# Esquematico.net
KiCad netlist of a schematic drawn in Altium Designer
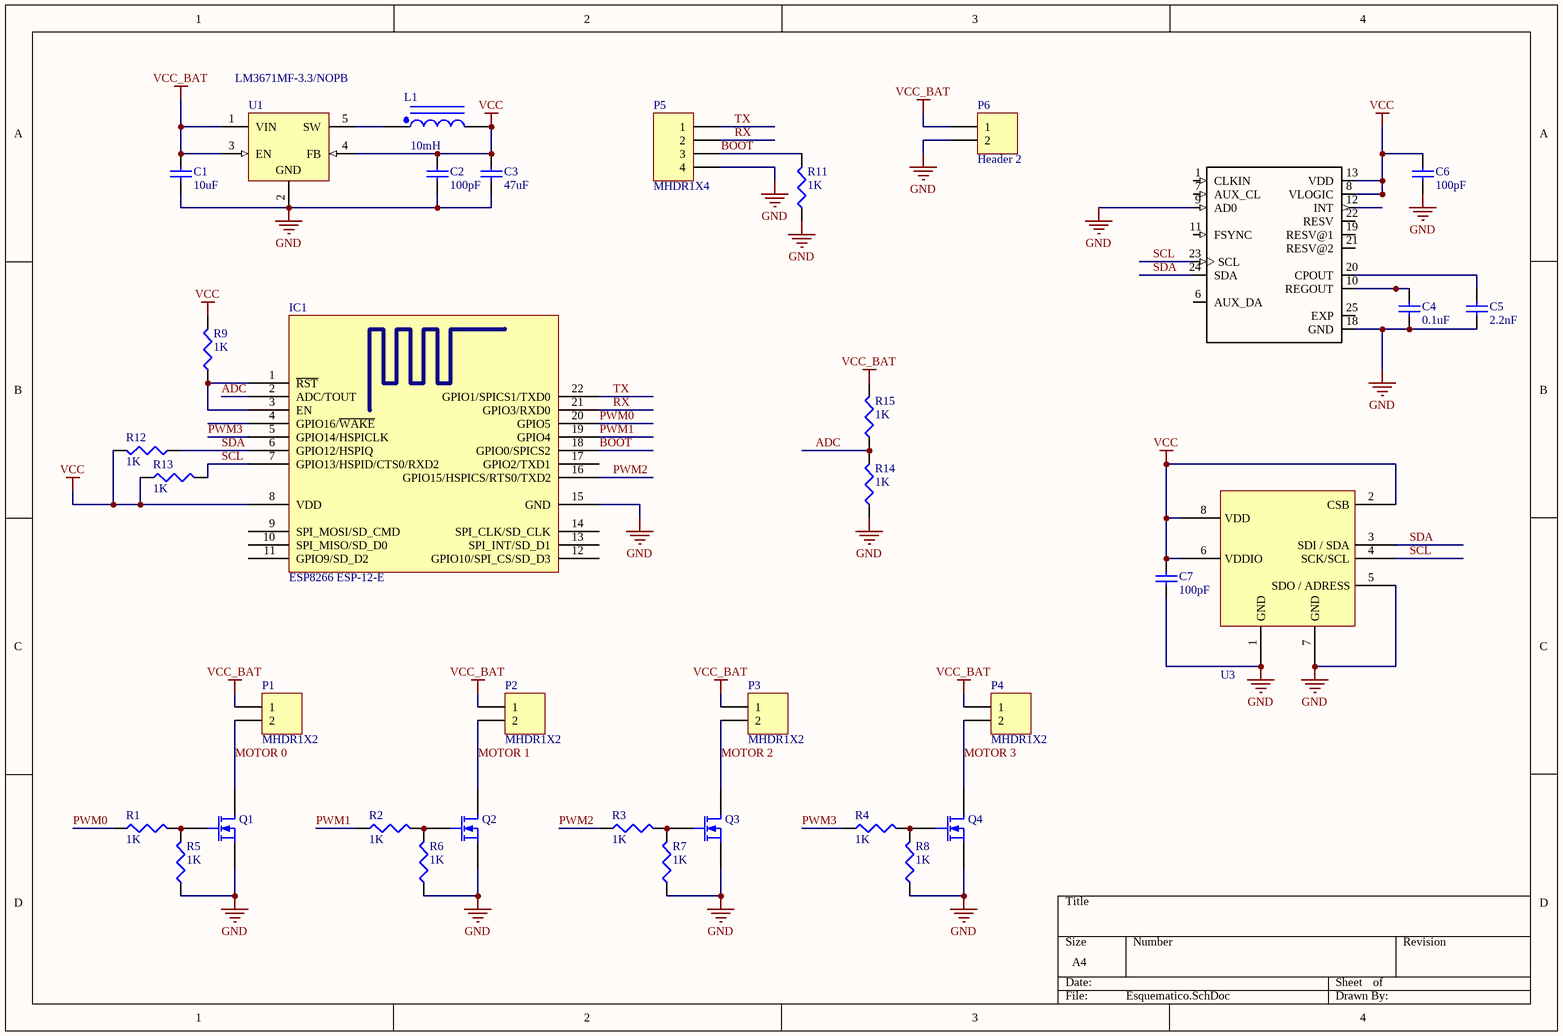
[diagram p0: Esquematico.SchDoc]

(export (version "E")
  (design (tool "Eeschema 10.0.6"))
  (components
    (comp (ref "C1")
      (value "10uF")
      (footprint "Miscellaneous Devices:6-0805_L")
      (description "Capacitor")
      (fields (field (name "Comment") "Cap") (field (name "PUBLISHER") "Altium Limited"))
      (libsource (lib "Miscellaneous Devices") (part "Cap"))
    )
    (comp (ref "C2")
      (value "100pF")
      (footprint "Miscellaneous Devices:6-0805_L")
      (description "Capacitor")
      (fields (field (name "Comment") "Cap") (field (name "PUBLISHER") "Altium Limited"))
      (libsource (lib "Miscellaneous Devices") (part "Cap"))
    )
    (comp (ref "C3")
      (value "47uF")
      (footprint "Miscellaneous Devices:6-0805_L")
      (description "Capacitor")
      (fields (field (name "Comment") "Cap") (field (name "PUBLISHER") "Altium Limited"))
      (libsource (lib "Miscellaneous Devices") (part "Cap"))
    )
    (comp (ref "C4")
      (value "0.1uF")
      (footprint "Miscellaneous Devices:6-0805_L")
      (description "Capacitor")
      (fields (field (name "Comment") "Cap") (field (name "PUBLISHER") "Altium Limited"))
      (libsource (lib "Miscellaneous Devices") (part "Cap"))
    )
    (comp (ref "C5")
      (value "2.2nF")
      (footprint "Miscellaneous Devices:6-0805_L")
      (description "Capacitor")
      (fields (field (name "Comment") "Cap") (field (name "PUBLISHER") "Altium Limited"))
      (libsource (lib "Miscellaneous Devices") (part "Cap"))
    )
    (comp (ref "C6")
      (value "100pF")
      (footprint "Miscellaneous Devices:6-0805_L")
      (description "Capacitor")
      (fields (field (name "Comment") "Cap") (field (name "PUBLISHER") "Altium Limited"))
      (libsource (lib "Miscellaneous Devices") (part "Cap"))
    )
    (comp (ref "C7")
      (value "100pF")
      (footprint "Miscellaneous Devices:6-0805_L")
      (description "Capacitor")
      (fields (field (name "Comment") "Cap") (field (name "PUBLISHER") "Altium Limited"))
      (libsource (lib "Miscellaneous Devices") (part "Cap"))
    )
    (comp (ref "IC1")
      (value "ESP8266 ESP-12-E")
      (footprint "ESP8266:ESP8266 ESP-12-E B")
      (libsource (lib "ESP8266") (part "ESP8266 ESP-12-E"))
    )
    (comp (ref "L1")
      (value "10mH")
      (footprint "Inductor CD43")
      (description "Magnetic-Core Inductor with Winding Polarity Marking")
      (fields (field (name "Comment") "Inductor Iron Dot") (field (name "PUBLISHER") "Altium Limited"))
      (libsource (lib "Miscellaneous Devices") (part "Inductor Iron Dot"))
    )
    (comp (ref "P1")
      (value "MHDR1X2")
      (footprint "MHDR1X2")
      (description "Header, 2-Pin")
      (fields (field (name "PUBLISHER") "Altium Limited"))
      (libsource (lib "Miscellaneous Connectors") (part "MHDR1X2"))
    )
    (comp (ref "P2")
      (value "MHDR1X2")
      (footprint "MHDR1X2")
      (description "Header, 2-Pin")
      (fields (field (name "PUBLISHER") "Altium Limited"))
      (libsource (lib "Miscellaneous Connectors") (part "MHDR1X2"))
    )
    (comp (ref "P3")
      (value "MHDR1X2")
      (footprint "MHDR1X2")
      (description "Header, 2-Pin")
      (fields (field (name "PUBLISHER") "Altium Limited"))
      (libsource (lib "Miscellaneous Connectors") (part "MHDR1X2"))
    )
    (comp (ref "P4")
      (value "MHDR1X2")
      (footprint "MHDR1X2")
      (description "Header, 2-Pin")
      (fields (field (name "PUBLISHER") "Altium Limited"))
      (libsource (lib "Miscellaneous Connectors") (part "MHDR1X2"))
    )
    (comp (ref "P5")
      (value "MHDR1X4")
      (footprint "MHDR1X4")
      (description "Header, 4-Pin")
      (fields (field (name "PUBLISHER") "Altium Limited"))
      (libsource (lib "Miscellaneous Connectors") (part "MHDR1X4"))
    )
    (comp (ref "P6")
      (value "Header 2")
      (footprint "HDR1X2")
      (description "Header, 2-Pin")
      (fields (field (name "PUBLISHER") "Altium Limited"))
      (libsource (lib "Miscellaneous Connectors") (part "Header 2"))
    )
    (comp (ref "Q1")
      (value "MOSFET-N")
      (footprint "PBL - SMD Packages:SOT23-3")
      (description "N-Channel MOSFET")
      (fields (field (name "PUBLISHER") "Altium Limited"))
      (libsource (lib "Miscellaneous Devices") (part "MOSFET-N"))
    )
    (comp (ref "Q2")
      (value "MOSFET-N")
      (footprint "PBL - SMD Packages:SOT23-3")
      (description "N-Channel MOSFET")
      (fields (field (name "PUBLISHER") "Altium Limited"))
      (libsource (lib "Miscellaneous Devices") (part "MOSFET-N"))
    )
    (comp (ref "Q3")
      (value "MOSFET-N")
      (footprint "PBL - SMD Packages:SOT23-3")
      (description "N-Channel MOSFET")
      (fields (field (name "PUBLISHER") "Altium Limited"))
      (libsource (lib "Miscellaneous Devices") (part "MOSFET-N"))
    )
    (comp (ref "Q4")
      (value "MOSFET-N")
      (footprint "PBL - SMD Packages:SOT23-3")
      (description "N-Channel MOSFET")
      (fields (field (name "PUBLISHER") "Altium Limited"))
      (libsource (lib "Miscellaneous Devices") (part "MOSFET-N"))
    )
    (comp (ref "R1")
      (value "1K")
      (footprint "6-0805_N")
      (description "Resistor")
      (fields (field (name "Comment") "Res3") (field (name "PUBLISHER") "Altium Limited"))
      (libsource (lib "Miscellaneous Devices") (part "Res3"))
    )
    (comp (ref "R2")
      (value "1K")
      (footprint "6-0805_N")
      (description "Resistor")
      (fields (field (name "Comment") "Res3") (field (name "PUBLISHER") "Altium Limited"))
      (libsource (lib "Miscellaneous Devices") (part "Res3"))
    )
    (comp (ref "R3")
      (value "1K")
      (footprint "6-0805_N")
      (description "Resistor")
      (fields (field (name "Comment") "Res3") (field (name "PUBLISHER") "Altium Limited"))
      (libsource (lib "Miscellaneous Devices") (part "Res3"))
    )
    (comp (ref "R4")
      (value "1K")
      (footprint "6-0805_N")
      (description "Resistor")
      (fields (field (name "Comment") "Res3") (field (name "PUBLISHER") "Altium Limited"))
      (libsource (lib "Miscellaneous Devices") (part "Res3"))
    )
    (comp (ref "R5")
      (value "1K")
      (footprint "6-0805_N")
      (description "Resistor")
      (fields (field (name "Comment") "Res3") (field (name "PUBLISHER") "Altium Limited"))
      (libsource (lib "Miscellaneous Devices") (part "Res3"))
    )
    (comp (ref "R6")
      (value "1K")
      (footprint "6-0805_N")
      (description "Resistor")
      (fields (field (name "Comment") "Res3") (field (name "PUBLISHER") "Altium Limited"))
      (libsource (lib "Miscellaneous Devices") (part "Res3"))
    )
    (comp (ref "R7")
      (value "1K")
      (footprint "6-0805_N")
      (description "Resistor")
      (fields (field (name "Comment") "Res3") (field (name "PUBLISHER") "Altium Limited"))
      (libsource (lib "Miscellaneous Devices") (part "Res3"))
    )
    (comp (ref "R8")
      (value "1K")
      (footprint "6-0805_N")
      (description "Resistor")
      (fields (field (name "Comment") "Res3") (field (name "PUBLISHER") "Altium Limited"))
      (libsource (lib "Miscellaneous Devices") (part "Res3"))
    )
    (comp (ref "R9")
      (value "1K")
      (footprint "Miscellaneous Devices:6-0805_L")
      (description "Resistor")
      (fields (field (name "Comment") "Res3") (field (name "PUBLISHER") "Altium Limited"))
      (libsource (lib "Miscellaneous Devices") (part "Res3"))
    )
    (comp (ref "R11")
      (value "1K")
      (footprint "Miscellaneous Devices:6-0805_L")
      (description "Resistor")
      (fields (field (name "Comment") "Res3") (field (name "PUBLISHER") "Altium Limited"))
      (libsource (lib "Miscellaneous Devices") (part "Res3"))
    )
    (comp (ref "R12")
      (value "1K")
      (footprint "Miscellaneous Devices:6-0805_L")
      (description "Resistor")
      (fields (field (name "Comment") "Res3") (field (name "PUBLISHER") "Altium Limited"))
      (libsource (lib "Miscellaneous Devices") (part "Res3"))
    )
    (comp (ref "R13")
      (value "1K")
      (footprint "Miscellaneous Devices:6-0805_L")
      (description "Resistor")
      (fields (field (name "Comment") "Res3") (field (name "PUBLISHER") "Altium Limited"))
      (libsource (lib "Miscellaneous Devices") (part "Res3"))
    )
    (comp (ref "R14")
      (value "1K")
      (footprint "Miscellaneous Devices:6-0805_L")
      (description "Resistor")
      (fields (field (name "Comment") "Res3") (field (name "PUBLISHER") "Altium Limited"))
      (libsource (lib "Miscellaneous Devices") (part "Res3"))
    )
    (comp (ref "R15")
      (value "1K")
      (footprint "Miscellaneous Devices:6-0805_L")
      (description "Resistor")
      (fields (field (name "Comment") "Res3") (field (name "PUBLISHER") "Altium Limited"))
      (libsource (lib "Miscellaneous Devices") (part "Res3"))
    )
    (comp (ref "U1")
      (value "LM3671MF-3.3/NOPB")
      (footprint "MF05A_N")
      (description "2MHz, 600mA Step-Down DC-DC Converter, 5-pin SOT-23, Pb-Free")
      (fields
        (field (name "MANUFACTURER") "National Semiconductor")
        (field (name "PUBLISHER") "Altium Limited")
      )
      (libsource (lib "NSC MiscPower") (part "LM3671MF-3.3/NOPB"))
    )
    (comp (ref "U2")
      (value "MPU-6050")
      (footprint "QFN50P400X400X95-25N")
      (libsource (lib "MPU-6050") (part "MPU-6050"))
    )
    (comp (ref "U3")
      (value "BMP280")
      (footprint "LGA-8_BMP280(Primary)")
      (description "Barometro")
      (libsource (lib "BMP280") (part "BMP280"))
    )
  )
  (nets
    (net (code "1") (name "/ADC") (class "Default")
      (node (ref "IC1") (pin "2") (pinfunction "ADC/TOUT_2") (pintype "passive"))
      (node (ref "R14") (pin "2") (pinfunction "2_2") (pintype "passive"))
      (node (ref "R15") (pin "1") (pinfunction "1_1") (pintype "passive"))
    )
    (net (code "2") (name "/BOOT") (class "Default")
      (node (ref "IC1") (pin "18") (pinfunction "GPIO0/SPICS2_18") (pintype "passive"))
      (node (ref "P5") (pin "3") (pinfunction "3_3") (pintype "passive"))
      (node (ref "R11") (pin "2") (pinfunction "2_2") (pintype "passive"))
    )
    (net (code "3") (name "/MOTOR 0") (class "Default")
      (node (ref "P1") (pin "2") (pinfunction "2_2") (pintype "passive"))
      (node (ref "Q1") (pin "1") (pinfunction "D_1") (pintype "passive"))
    )
    (net (code "4") (name "/MOTOR 1") (class "Default")
      (node (ref "P2") (pin "2") (pinfunction "2_2") (pintype "passive"))
      (node (ref "Q2") (pin "1") (pinfunction "D_1") (pintype "passive"))
    )
    (net (code "5") (name "/MOTOR 2") (class "Default")
      (node (ref "P3") (pin "2") (pinfunction "2_2") (pintype "passive"))
      (node (ref "Q3") (pin "1") (pinfunction "D_1") (pintype "passive"))
    )
    (net (code "6") (name "/MOTOR 3") (class "Default")
      (node (ref "P4") (pin "2") (pinfunction "2_2") (pintype "passive"))
      (node (ref "Q4") (pin "1") (pinfunction "D_1") (pintype "passive"))
    )
    (net (code "7") (name "/PWM0") (class "Default")
      (node (ref "IC1") (pin "20") (pinfunction "GPIO5_20") (pintype "passive"))
      (node (ref "R1") (pin "1") (pinfunction "1_1") (pintype "passive"))
    )
    (net (code "8") (name "/PWM1") (class "Default")
      (node (ref "IC1") (pin "19") (pinfunction "GPIO4_19") (pintype "passive"))
      (node (ref "R2") (pin "1") (pinfunction "1_1") (pintype "passive"))
    )
    (net (code "9") (name "/PWM2") (class "Default")
      (node (ref "IC1") (pin "16") (pinfunction "GPIO15/HSPICS/RTS0/TXD2_16") (pintype "passive"))
      (node (ref "R3") (pin "1") (pinfunction "1_1") (pintype "passive"))
    )
    (net (code "10") (name "/PWM3") (class "Default")
      (node (ref "IC1") (pin "5") (pinfunction "GPIO14/HSPICLK_5") (pintype "passive"))
      (node (ref "R4") (pin "1") (pinfunction "1_1") (pintype "passive"))
    )
    (net (code "11") (name "/RX") (class "Default")
      (node (ref "IC1") (pin "21") (pinfunction "GPIO3/RXD0_21") (pintype "passive"))
      (node (ref "P5") (pin "2") (pinfunction "2_2") (pintype "passive"))
    )
    (net (code "12") (name "/SCL") (class "Default")
      (node (ref "IC1") (pin "7") (pinfunction "GPIO13/HSPID/CTS0/RXD2_7") (pintype "passive"))
      (node (ref "R13") (pin "2") (pinfunction "2_2") (pintype "passive"))
      (node (ref "U2") (pin "23") (pinfunction "SCL_23") (pintype "input"))
      (node (ref "U3") (pin "4") (pinfunction "SCK/SCL_4") (pintype "passive"))
    )
    (net (code "13") (name "/SDA") (class "Default")
      (node (ref "IC1") (pin "6") (pinfunction "GPIO12/HSPIQ_6") (pintype "passive"))
      (node (ref "R12") (pin "1") (pinfunction "1_1") (pintype "passive"))
      (node (ref "U2") (pin "24") (pinfunction "SDA_24") (pintype "bidirectional"))
      (node (ref "U3") (pin "3") (pinfunction "SDI_/_SDA_3") (pintype "passive"))
    )
    (net (code "14") (name "/TX") (class "Default")
      (node (ref "IC1") (pin "22") (pinfunction "GPIO1/SPICS1/TXD0_22") (pintype "passive"))
      (node (ref "P5") (pin "1") (pinfunction "1_1") (pintype "passive"))
    )
    (net (code "15") (name "GND") (class "Default")
      (node (ref "C1") (pin "1") (pinfunction "1_1") (pintype "passive"))
      (node (ref "C2") (pin "1") (pinfunction "1_1") (pintype "passive"))
      (node (ref "C3") (pin "1") (pinfunction "1_1") (pintype "passive"))
      (node (ref "C4") (pin "1") (pinfunction "1_1") (pintype "passive"))
      (node (ref "C5") (pin "1") (pinfunction "1_1") (pintype "passive"))
      (node (ref "C6") (pin "1") (pinfunction "1_1") (pintype "passive"))
      (node (ref "C7") (pin "1") (pinfunction "1_1") (pintype "passive"))
      (node (ref "IC1") (pin "15") (pinfunction "GND_15") (pintype "passive"))
      (node (ref "P5") (pin "4") (pinfunction "4_4") (pintype "passive"))
      (node (ref "P6") (pin "2") (pinfunction "2_2") (pintype "passive"))
      (node (ref "Q1") (pin "3") (pinfunction "S_3") (pintype "passive"))
      (node (ref "Q2") (pin "3") (pinfunction "S_3") (pintype "passive"))
      (node (ref "Q3") (pin "3") (pinfunction "S_3") (pintype "passive"))
      (node (ref "Q4") (pin "3") (pinfunction "S_3") (pintype "passive"))
      (node (ref "R11") (pin "1") (pinfunction "1_1") (pintype "passive"))
      (node (ref "R14") (pin "1") (pinfunction "1_1") (pintype "passive"))
      (node (ref "R5") (pin "1") (pinfunction "1_1") (pintype "passive"))
      (node (ref "R6") (pin "1") (pinfunction "1_1") (pintype "passive"))
      (node (ref "R7") (pin "1") (pinfunction "1_1") (pintype "passive"))
      (node (ref "R8") (pin "1") (pinfunction "1_1") (pintype "passive"))
      (node (ref "U1") (pin "2") (pinfunction "GND_2") (pintype "power_in"))
      (node (ref "U2") (pin "18") (pinfunction "GND_18") (pintype "power_in"))
      (node (ref "U2") (pin "9") (pinfunction "AD0_9") (pintype "input"))
      (node (ref "U3") (pin "1") (pinfunction "GND_1") (pintype "passive"))
      (node (ref "U3") (pin "5") (pinfunction "SDO_/_ADRESS_5") (pintype "passive"))
      (node (ref "U3") (pin "7") (pinfunction "GND_7") (pintype "passive"))
    )
    (net (code "16") (name "Net-(IC1-EN)") (class "Default")
      (node (ref "IC1") (pin "1") (pinfunction "~{RST}_1") (pintype "passive"))
      (node (ref "IC1") (pin "3") (pinfunction "EN_3") (pintype "passive"))
      (node (ref "R9") (pin "1") (pinfunction "1_1") (pintype "passive"))
    )
    (net (code "17") (name "Net-(Q1-G)") (class "Default")
      (node (ref "Q1") (pin "2") (pinfunction "G_2") (pintype "passive"))
      (node (ref "R1") (pin "2") (pinfunction "2_2") (pintype "passive"))
      (node (ref "R5") (pin "2") (pinfunction "2_2") (pintype "passive"))
    )
    (net (code "18") (name "Net-(Q2-G)") (class "Default")
      (node (ref "Q2") (pin "2") (pinfunction "G_2") (pintype "passive"))
      (node (ref "R2") (pin "2") (pinfunction "2_2") (pintype "passive"))
      (node (ref "R6") (pin "2") (pinfunction "2_2") (pintype "passive"))
    )
    (net (code "19") (name "Net-(Q3-G)") (class "Default")
      (node (ref "Q3") (pin "2") (pinfunction "G_2") (pintype "passive"))
      (node (ref "R3") (pin "2") (pinfunction "2_2") (pintype "passive"))
      (node (ref "R7") (pin "2") (pinfunction "2_2") (pintype "passive"))
    )
    (net (code "20") (name "Net-(Q4-G)") (class "Default")
      (node (ref "Q4") (pin "2") (pinfunction "G_2") (pintype "passive"))
      (node (ref "R4") (pin "2") (pinfunction "2_2") (pintype "passive"))
      (node (ref "R8") (pin "2") (pinfunction "2_2") (pintype "passive"))
    )
    (net (code "21") (name "Net-(U1-SW)") (class "Default")
      (node (ref "L1") (pin "1") (pinfunction "1_1") (pintype "passive"))
      (node (ref "U1") (pin "5") (pinfunction "SW_5") (pintype "power_in"))
    )
    (net (code "22") (name "Net-(U2-CPOUT)") (class "Default")
      (node (ref "C5") (pin "2") (pinfunction "2_2") (pintype "passive"))
      (node (ref "U2") (pin "20") (pinfunction "CPOUT_20") (pintype "passive"))
    )
    (net (code "23") (name "Net-(U2-REGOUT)") (class "Default")
      (node (ref "C4") (pin "2") (pinfunction "2_2") (pintype "passive"))
      (node (ref "U2") (pin "10") (pinfunction "REGOUT_10") (pintype "passive"))
    )
    (net (code "24") (name "VCC") (class "Default")
      (node (ref "C2") (pin "2") (pinfunction "2_2") (pintype "passive"))
      (node (ref "C3") (pin "2") (pinfunction "2_2") (pintype "passive"))
      (node (ref "C6") (pin "2") (pinfunction "2_2") (pintype "passive"))
      (node (ref "C7") (pin "2") (pinfunction "2_2") (pintype "passive"))
      (node (ref "IC1") (pin "8") (pinfunction "VDD_8") (pintype "passive"))
      (node (ref "L1") (pin "2") (pinfunction "2_2") (pintype "passive"))
      (node (ref "R12") (pin "2") (pinfunction "2_2") (pintype "passive"))
      (node (ref "R13") (pin "1") (pinfunction "1_1") (pintype "passive"))
      (node (ref "R9") (pin "2") (pinfunction "2_2") (pintype "passive"))
      (node (ref "U1") (pin "4") (pinfunction "FB_4") (pintype "input"))
      (node (ref "U2") (pin "13") (pinfunction "VDD_13") (pintype "power_in"))
      (node (ref "U2") (pin "8") (pinfunction "VLOGIC_8") (pintype "power_in"))
      (node (ref "U3") (pin "2") (pinfunction "CSB_2") (pintype "passive"))
      (node (ref "U3") (pin "6") (pinfunction "VDDIO_6") (pintype "passive"))
      (node (ref "U3") (pin "8") (pinfunction "VDD_8") (pintype "passive"))
    )
    (net (code "25") (name "VCC_BAT") (class "Default")
      (node (ref "C1") (pin "2") (pinfunction "2_2") (pintype "passive"))
      (node (ref "P1") (pin "1") (pinfunction "1_1") (pintype "passive"))
      (node (ref "P2") (pin "1") (pinfunction "1_1") (pintype "passive"))
      (node (ref "P3") (pin "1") (pinfunction "1_1") (pintype "passive"))
      (node (ref "P4") (pin "1") (pinfunction "1_1") (pintype "passive"))
      (node (ref "P6") (pin "1") (pinfunction "1_1") (pintype "passive"))
      (node (ref "R15") (pin "2") (pinfunction "2_2") (pintype "passive"))
      (node (ref "U1") (pin "1") (pinfunction "VIN_1") (pintype "power_in"))
      (node (ref "U1") (pin "3") (pinfunction "EN_3") (pintype "input"))
    )
    (net (code "26") (name "unconnected-(IC1-GPIO2{slash}TXD1-Pad17)") (class "Default")
      (node (ref "IC1") (pin "17") (pinfunction "GPIO2/TXD1_17") (pintype "passive"))
    )
    (net (code "27") (name "unconnected-(IC1-GPIO9{slash}SD_D2-Pad11)") (class "Default")
      (node (ref "IC1") (pin "11") (pinfunction "GPIO9/SD_D2_11") (pintype "passive"))
    )
    (net (code "28") (name "unconnected-(IC1-GPIO10{slash}SPI_CS{slash}SD_D3-Pad12)") (class "Default")
      (node (ref "IC1") (pin "12") (pinfunction "GPIO10/SPI_CS/SD_D3_12") (pintype "passive"))
    )
    (net (code "29") (name "unconnected-(IC1-GPIO16{slash}~{WAKE}-Pad4)") (class "Default")
      (node (ref "IC1") (pin "4") (pinfunction "GPIO16/~{WAKE}_4") (pintype "passive"))
    )
    (net (code "30") (name "unconnected-(IC1-SPI_CLK{slash}SD_CLK-Pad14)") (class "Default")
      (node (ref "IC1") (pin "14") (pinfunction "SPI_CLK/SD_CLK_14") (pintype "passive"))
    )
    (net (code "31") (name "unconnected-(IC1-SPI_INT{slash}SD_D1-Pad13)") (class "Default")
      (node (ref "IC1") (pin "13") (pinfunction "SPI_INT/SD_D1_13") (pintype "passive"))
    )
    (net (code "32") (name "unconnected-(IC1-SPI_MISO{slash}SD_D0-Pad10)") (class "Default")
      (node (ref "IC1") (pin "10") (pinfunction "SPI_MISO/SD_D0_10") (pintype "passive"))
    )
    (net (code "33") (name "unconnected-(IC1-SPI_MOSI{slash}SD_CMD-Pad9)") (class "Default")
      (node (ref "IC1") (pin "9") (pinfunction "SPI_MOSI/SD_CMD_9") (pintype "passive"))
    )
    (net (code "34") (name "unconnected-(U2-AUX_CL-Pad7)") (class "Default")
      (node (ref "U2") (pin "7") (pinfunction "AUX_CL_7") (pintype "input"))
    )
    (net (code "35") (name "unconnected-(U2-AUX_DA-Pad6)") (class "Default")
      (node (ref "U2") (pin "6") (pinfunction "AUX_DA_6") (pintype "bidirectional"))
    )
    (net (code "36") (name "unconnected-(U2-CLKIN-Pad1)") (class "Default")
      (node (ref "U2") (pin "1") (pinfunction "CLKIN_1") (pintype "input"))
    )
    (net (code "37") (name "unconnected-(U2-EXP-Pad25)") (class "Default")
      (node (ref "U2") (pin "25") (pinfunction "EXP_25") (pintype "power_in"))
    )
    (net (code "38") (name "unconnected-(U2-FSYNC-Pad11)") (class "Default")
      (node (ref "U2") (pin "11") (pinfunction "FSYNC_11") (pintype "input"))
    )
    (net (code "39") (name "unconnected-(U2-INT-Pad12)") (class "Default")
      (node (ref "U2") (pin "12") (pinfunction "INT_12") (pintype "output"))
    )
    (net (code "40") (name "unconnected-(U2-RESV-Pad22)") (class "Default")
      (node (ref "U2") (pin "22") (pinfunction "RESV_22") (pintype "passive"))
    )
    (net (code "41") (name "unconnected-(U2-RESV@1-Pad19)") (class "Default")
      (node (ref "U2") (pin "19") (pinfunction "RESV@1_19") (pintype "passive"))
    )
    (net (code "42") (name "unconnected-(U2-RESV@2-Pad21)") (class "Default")
      (node (ref "U2") (pin "21") (pinfunction "RESV@2_21") (pintype "passive"))
    )
  )
)
